# pro_micro_adapter.net
KiCad netlist of a schematic drawn in EAGLE
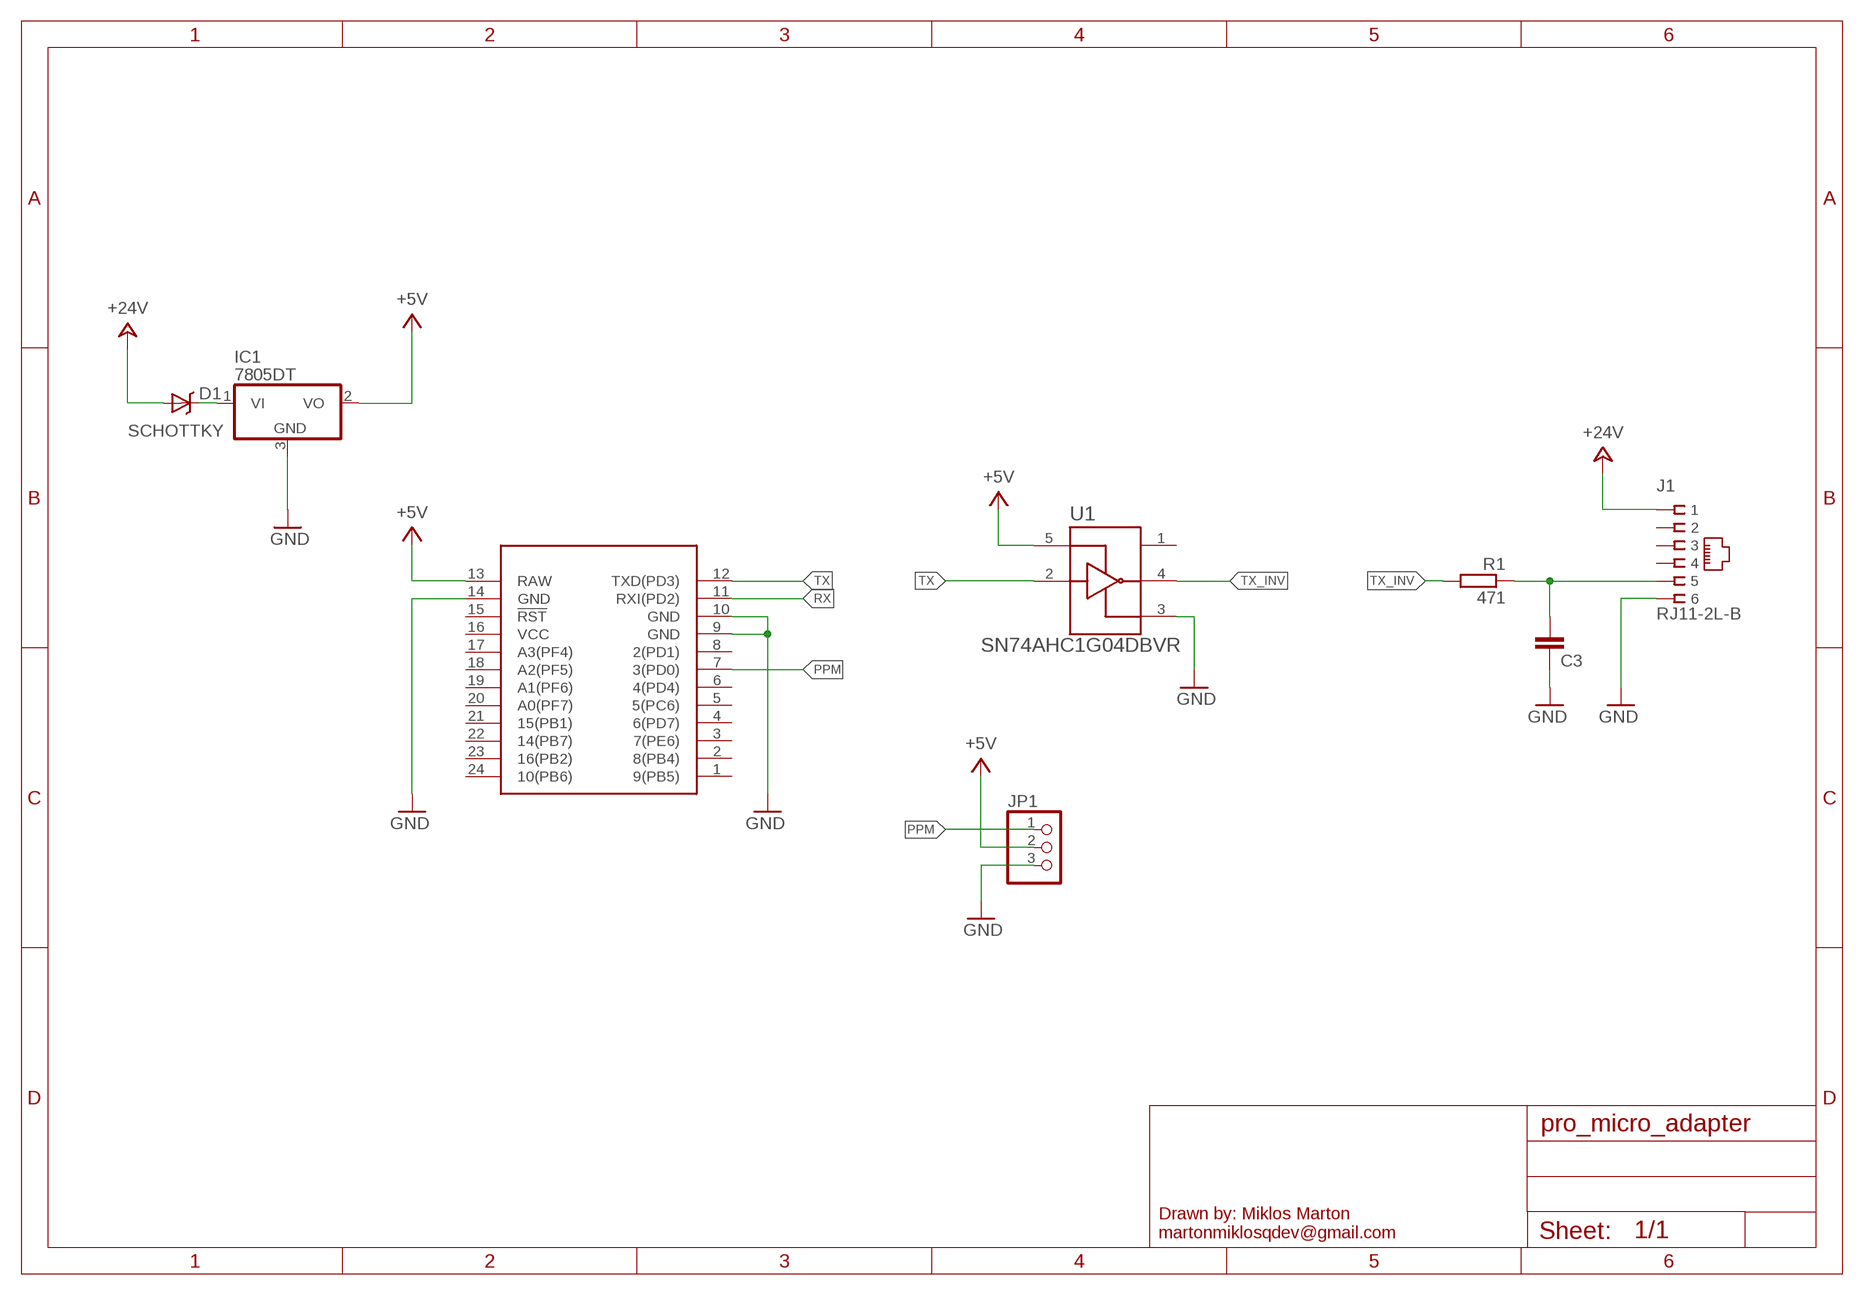
[diagram p0: schematic, sheet 1]

(export (version "E")
  (design (tool "Eeschema 10.0.6"))
  (components
    (comp (ref "C3")
      (value "C-EUC0805")
      (footprint "eagle-import:C0805")
      (libsource (lib "eagle-import") (part "C-EUC0805"))
    )
    (comp (ref "D1")
      (value "SCHOTTKY")
      (footprint "eagle-import:DO-214AC")
      (libsource (lib "eagle-import") (part "SCHOTTKY"))
    )
    (comp (ref "IC1")
      (value "7805DT")
      (footprint "eagle-import:TO252")
      (libsource (lib "eagle-import") (part "78DT05"))
    )
    (comp (ref "J1")
      (value "RJ11-2L-B")
      (footprint "eagle-import:RJ11-NO_SHIELD")
      (fields (field (name "MF") "TYCO ELECTRONICS"))
      (libsource (lib "eagle-import") (part "RJ11-2L-B"))
    )
    (comp (ref "JP1")
      (value "PINHD-1X3")
      (footprint "eagle-import:1X03")
      (libsource (lib "eagle-import") (part "PINHD-1X3"))
    )
    (comp (ref "R1")
      (value "471")
      (footprint "eagle-import:R0805")
      (libsource (lib "eagle-import") (part "R-EU_R0805"))
    )
    (comp (ref "U$1")
      (value "ARDUINO_MICRO_PRO")
      (footprint "eagle-import:ARDUINO_MICRO_PRO")
      (libsource (lib "eagle-import") (part "ARDUINO_MICRO_PRO"))
    )
    (comp (ref "U1")
      (value "SN74AHC1G04DBVR")
      (footprint "eagle-import:SOT95P280X145-5N")
      (fields (field (name "MF") "Texas Instruments"))
      (libsource (lib "eagle-import") (part "SN74AHC1G04DBVR"))
    )
  )
  (nets
    (net (code "1") (name "+5V") (class "Default")
      (node (ref "IC1") (pin "2") (pinfunction "VO_2") (pintype "passive"))
      (node (ref "JP1") (pin "2") (pinfunction "2_2") (pintype "passive"))
      (node (ref "U$1") (pin "13") (pinfunction "RAW_13") (pintype "power_in"))
      (node (ref "U1") (pin "5") (pinfunction "VCC_5") (pintype "power_in"))
    )
    (net (code "2") (name "+24V") (class "Default")
      (node (ref "D1") (pin "A") (pinfunction "A_A") (pintype "passive"))
      (node (ref "J1") (pin "1") (pinfunction "1_1") (pintype "passive"))
    )
    (net (code "3") (name "/VCC") (class "Default")
      (node (ref "U$1") (pin "16") (pinfunction "VCC_16") (pintype "power_in"))
    )
    (net (code "4") (name "GND") (class "Default")
      (node (ref "C3") (pin "1") (pinfunction "1_1") (pintype "passive"))
      (node (ref "IC1") (pin "3") (pinfunction "GND_3") (pintype "passive"))
      (node (ref "J1") (pin "6") (pinfunction "6_6") (pintype "passive"))
      (node (ref "JP1") (pin "3") (pinfunction "3_3") (pintype "passive"))
      (node (ref "U$1") (pin "10") (pinfunction "GND_10") (pintype "passive"))
      (node (ref "U$1") (pin "14") (pinfunction "GND_14") (pintype "passive"))
      (node (ref "U$1") (pin "9") (pinfunction "GND_9") (pintype "passive"))
      (node (ref "U1") (pin "3") (pinfunction "GND_3") (pintype "power_in"))
    )
    (net (code "5") (name "Net-(C3-Pad2)") (class "Default")
      (node (ref "C3") (pin "2") (pinfunction "2_2") (pintype "passive"))
      (node (ref "J1") (pin "5") (pinfunction "5_5") (pintype "passive"))
      (node (ref "R1") (pin "1") (pinfunction "1_1") (pintype "passive"))
    )
    (net (code "6") (name "Net-(IC1-VI)") (class "Default")
      (node (ref "D1") (pin "C") (pinfunction "C_C") (pintype "passive"))
      (node (ref "IC1") (pin "1") (pinfunction "VI_1") (pintype "input"))
    )
    (net (code "7") (name "PPM") (class "Default")
      (node (ref "JP1") (pin "1") (pinfunction "1_1") (pintype "passive"))
      (node (ref "U$1") (pin "7") (pinfunction "3(PD0)_7") (pintype "bidirectional"))
    )
    (net (code "8") (name "RX") (class "Default")
      (node (ref "U$1") (pin "11") (pinfunction "RXI(PD2)_11") (pintype "input"))
    )
    (net (code "9") (name "TX") (class "Default")
      (node (ref "U$1") (pin "12") (pinfunction "TXD(PD3)_12") (pintype "output"))
      (node (ref "U1") (pin "2") (pinfunction "A_2") (pintype "input"))
    )
    (net (code "10") (name "TX_INV") (class "Default")
      (node (ref "R1") (pin "2") (pinfunction "2_2") (pintype "passive"))
      (node (ref "U1") (pin "4") (pinfunction "Y_4") (pintype "output"))
    )
    (net (code "11") (name "unconnected-(J1-Pad2)") (class "Default")
      (node (ref "J1") (pin "2") (pinfunction "2_2") (pintype "passive"))
    )
    (net (code "12") (name "unconnected-(J1-Pad3)") (class "Default")
      (node (ref "J1") (pin "3") (pinfunction "3_3") (pintype "passive"))
    )
    (net (code "13") (name "unconnected-(J1-Pad4)") (class "Default")
      (node (ref "J1") (pin "4") (pinfunction "4_4") (pintype "passive"))
    )
    (net (code "14") (name "unconnected-(U$1-2(PD1)-Pad8)") (class "Default")
      (node (ref "U$1") (pin "8") (pinfunction "2(PD1)_8") (pintype "bidirectional"))
    )
    (net (code "15") (name "unconnected-(U$1-4(PD4)-Pad6)") (class "Default")
      (node (ref "U$1") (pin "6") (pinfunction "4(PD4)_6") (pintype "bidirectional"))
    )
    (net (code "16") (name "unconnected-(U$1-5(PC6)-Pad5)") (class "Default")
      (node (ref "U$1") (pin "5") (pinfunction "5(PC6)_5") (pintype "bidirectional"))
    )
    (net (code "17") (name "unconnected-(U$1-6(PD7)-Pad4)") (class "Default")
      (node (ref "U$1") (pin "4") (pinfunction "6(PD7)_4") (pintype "bidirectional"))
    )
    (net (code "18") (name "unconnected-(U$1-7(PE6)-Pad3)") (class "Default")
      (node (ref "U$1") (pin "3") (pinfunction "7(PE6)_3") (pintype "bidirectional"))
    )
    (net (code "19") (name "unconnected-(U$1-8(PB4)-Pad2)") (class "Default")
      (node (ref "U$1") (pin "2") (pinfunction "8(PB4)_2") (pintype "bidirectional"))
    )
    (net (code "20") (name "unconnected-(U$1-9(PB5)-Pad1)") (class "Default")
      (node (ref "U$1") (pin "1") (pinfunction "9(PB5)_1") (pintype "bidirectional"))
    )
    (net (code "21") (name "unconnected-(U$1-10(PB6)-Pad24)") (class "Default")
      (node (ref "U$1") (pin "24") (pinfunction "10(PB6)_24") (pintype "bidirectional"))
    )
    (net (code "22") (name "unconnected-(U$1-14(PB7)-Pad22)") (class "Default")
      (node (ref "U$1") (pin "22") (pinfunction "14(PB7)_22") (pintype "bidirectional"))
    )
    (net (code "23") (name "unconnected-(U$1-15(PB1)-Pad21)") (class "Default")
      (node (ref "U$1") (pin "21") (pinfunction "15(PB1)_21") (pintype "bidirectional"))
    )
    (net (code "24") (name "unconnected-(U$1-16(PB2)-Pad23)") (class "Default")
      (node (ref "U$1") (pin "23") (pinfunction "16(PB2)_23") (pintype "bidirectional"))
    )
    (net (code "25") (name "unconnected-(U$1-A0(PF7)-Pad20)") (class "Default")
      (node (ref "U$1") (pin "20") (pinfunction "A0(PF7)_20") (pintype "bidirectional"))
    )
    (net (code "26") (name "unconnected-(U$1-A1(PF6)-Pad19)") (class "Default")
      (node (ref "U$1") (pin "19") (pinfunction "A1(PF6)_19") (pintype "bidirectional"))
    )
    (net (code "27") (name "unconnected-(U$1-A2(PF5)-Pad18)") (class "Default")
      (node (ref "U$1") (pin "18") (pinfunction "A2(PF5)_18") (pintype "bidirectional"))
    )
    (net (code "28") (name "unconnected-(U$1-A3(PF4)-Pad17)") (class "Default")
      (node (ref "U$1") (pin "17") (pinfunction "A3(PF4)_17") (pintype "bidirectional"))
    )
    (net (code "29") (name "unconnected-(U$1-~{RST}-Pad15)") (class "Default")
      (node (ref "U$1") (pin "15") (pinfunction "~{RST}_15") (pintype "input"))
    )
    (net (code "30") (name "unconnected-(U1-NC-Pad1)") (class "Default")
      (node (ref "U1") (pin "1") (pinfunction "NC_1") (pintype "passive"))
    )
  )
)
